# gpio8p5.net
KiCad netlist of a schematic drawn in EAGLE
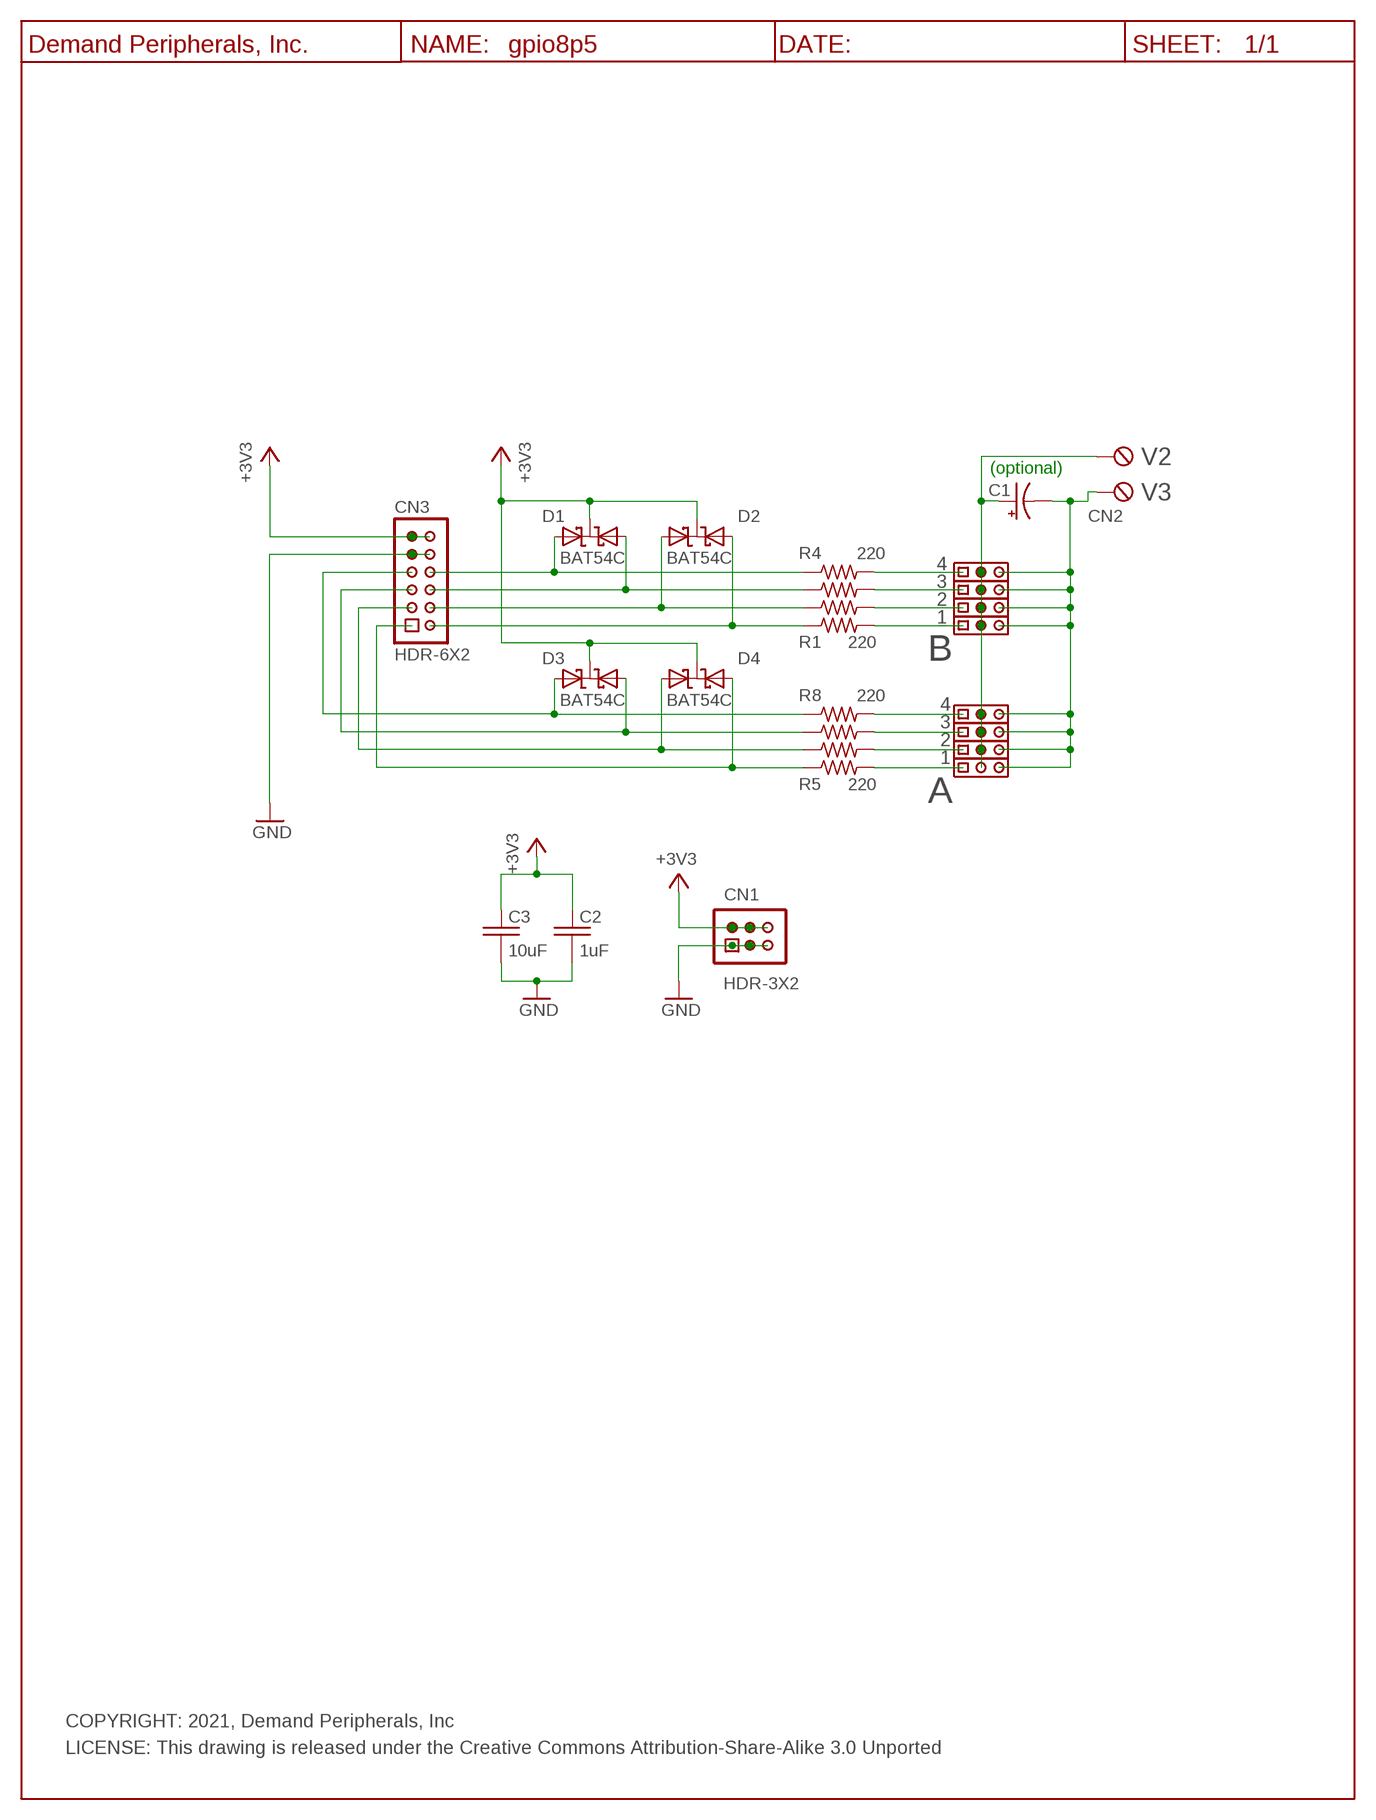
[diagram p0: schematic, sheet 1]

(export (version "E")
  (design (tool "Eeschema 10.0.6"))
  (components
    (comp (ref "C1")
      (value "100uF")
      (footprint "eagle-import:E3.5-8")
      (libsource (lib "eagle-import") (part "C100UF_E3.5-8"))
    )
    (comp (ref "C2")
      (value "1uF")
      (footprint "eagle-import:C0603")
      (libsource (lib "eagle-import") (part "C1.0UF_C0603"))
    )
    (comp (ref "C3")
      (value "10uF")
      (footprint "eagle-import:C1206")
      (libsource (lib "eagle-import") (part "C10UF25V_C1206"))
    )
    (comp (ref "CN1")
      (value "HDR-3X2")
      (footprint "eagle-import:HDR-3X2")
      (libsource (lib "eagle-import") (part "HDR-3X2"))
    )
    (comp (ref "CN2")
      (value "TBLK-5.08-X2")
      (footprint "eagle-import:TBLK-5.08-X2")
      (libsource (lib "eagle-import") (part "TBLK-5.08-X2"))
    )
    (comp (ref "CN3")
      (value "HDR-6X2")
      (footprint "eagle-import:HDR-6X2")
      (libsource (lib "eagle-import") (part "HDR-6X2"))
    )
    (comp (ref "D1")
      (value "BAT54C")
      (footprint "eagle-import:SOT23")
      (libsource (lib "eagle-import") (part "BAT54C"))
    )
    (comp (ref "D2")
      (value "BAT54C")
      (footprint "eagle-import:SOT23")
      (libsource (lib "eagle-import") (part "BAT54C"))
    )
    (comp (ref "D3")
      (value "BAT54C")
      (footprint "eagle-import:SOT23")
      (libsource (lib "eagle-import") (part "BAT54C"))
    )
    (comp (ref "D4")
      (value "BAT54C")
      (footprint "eagle-import:SOT23")
      (libsource (lib "eagle-import") (part "BAT54C"))
    )
    (comp (ref "R1")
      (value "220")
      (footprint "eagle-import:R0603")
      (libsource (lib "eagle-import") (part "R220_R0603"))
    )
    (comp (ref "R2")
      (value "220")
      (footprint "eagle-import:R0603")
      (libsource (lib "eagle-import") (part "R220_R0603"))
    )
    (comp (ref "R3")
      (value "220")
      (footprint "eagle-import:R0603")
      (libsource (lib "eagle-import") (part "R220_R0603"))
    )
    (comp (ref "R4")
      (value "220")
      (footprint "eagle-import:R0603")
      (libsource (lib "eagle-import") (part "R220_R0603"))
    )
    (comp (ref "R5")
      (value "220")
      (footprint "eagle-import:R0603")
      (libsource (lib "eagle-import") (part "R220_R0603"))
    )
    (comp (ref "R6")
      (value "220")
      (footprint "eagle-import:R0603")
      (libsource (lib "eagle-import") (part "R220_R0603"))
    )
    (comp (ref "R7")
      (value "220")
      (footprint "eagle-import:R0603")
      (libsource (lib "eagle-import") (part "R220_R0603"))
    )
    (comp (ref "R8")
      (value "220")
      (footprint "eagle-import:R0603")
      (libsource (lib "eagle-import") (part "R220_R0603"))
    )
    (comp (ref "U$1")
      (value "DP_FRAME_P")
      (footprint "eagle-import:P_FRAME")
      (libsource (lib "eagle-import") (part "DP_FRAME_P"))
    )
    (comp (ref "U$5")
      (value "HDR-3X1")
      (footprint "eagle-import:HDR-3X1")
      (libsource (lib "eagle-import") (part "HDR-3X1"))
    )
    (comp (ref "U$6")
      (value "HDR-3X1")
      (footprint "eagle-import:HDR-3X1")
      (libsource (lib "eagle-import") (part "HDR-3X1"))
    )
    (comp (ref "U$7")
      (value "HDR-3X1")
      (footprint "eagle-import:HDR-3X1")
      (libsource (lib "eagle-import") (part "HDR-3X1"))
    )
    (comp (ref "U$9")
      (value "HDR-3X1")
      (footprint "eagle-import:HDR-3X1")
      (libsource (lib "eagle-import") (part "HDR-3X1"))
    )
    (comp (ref "U$10")
      (value "HDR-3X1")
      (footprint "eagle-import:HDR-3X1")
      (libsource (lib "eagle-import") (part "HDR-3X1"))
    )
    (comp (ref "U$11")
      (value "HDR-3X1")
      (footprint "eagle-import:HDR-3X1")
      (libsource (lib "eagle-import") (part "HDR-3X1"))
    )
    (comp (ref "U$12")
      (value "HDR-3X1")
      (footprint "eagle-import:HDR-3X1")
      (libsource (lib "eagle-import") (part "HDR-3X1"))
    )
    (comp (ref "U$13")
      (value "HDR-3X1")
      (footprint "eagle-import:HDR-3X1")
      (libsource (lib "eagle-import") (part "HDR-3X1"))
    )
  )
  (nets
    (net (code "1") (name "+3V3") (class "Default")
      (node (ref "C2") (pin "1") (pinfunction "1_1") (pintype "passive"))
      (node (ref "C3") (pin "1") (pinfunction "1_1") (pintype "passive"))
      (node (ref "CN1") (pin "2") (pinfunction "2_2") (pintype "passive"))
      (node (ref "CN1") (pin "4") (pinfunction "4_4") (pintype "passive"))
      (node (ref "CN1") (pin "6") (pinfunction "6_6") (pintype "passive"))
      (node (ref "CN3") (pin "11") (pinfunction "11_11") (pintype "passive"))
      (node (ref "CN3") (pin "12") (pinfunction "12_12") (pintype "passive"))
      (node (ref "D1") (pin "3") (pinfunction "CC_3") (pintype "passive"))
      (node (ref "D2") (pin "3") (pinfunction "CC_3") (pintype "passive"))
      (node (ref "D3") (pin "3") (pinfunction "CC_3") (pintype "passive"))
      (node (ref "D4") (pin "3") (pinfunction "CC_3") (pintype "passive"))
    )
    (net (code "2") (name "GND") (class "Default")
      (node (ref "C2") (pin "2") (pinfunction "2_2") (pintype "passive"))
      (node (ref "C3") (pin "2") (pinfunction "2_2") (pintype "passive"))
      (node (ref "CN1") (pin "1") (pinfunction "1_1") (pintype "passive"))
      (node (ref "CN1") (pin "3") (pinfunction "3_3") (pintype "passive"))
      (node (ref "CN1") (pin "5") (pinfunction "5_5") (pintype "passive"))
      (node (ref "CN3") (pin "10") (pinfunction "10_10") (pintype "passive"))
      (node (ref "CN3") (pin "9") (pinfunction "9_9") (pintype "passive"))
    )
    (net (code "3") (name "Net-(CN2-KL)") (class "Default")
      (node (ref "C1") (pin "-") (pinfunction "-_-") (pintype "passive"))
      (node (ref "CN2") (pin "1") (pinfunction "KL_1") (pintype "passive"))
      (node (ref "U$10") (pin "3") (pinfunction "3_3") (pintype "passive"))
      (node (ref "U$11") (pin "3") (pinfunction "3_3") (pintype "passive"))
      (node (ref "U$12") (pin "3") (pinfunction "3_3") (pintype "passive"))
      (node (ref "U$13") (pin "3") (pinfunction "3_3") (pintype "passive"))
      (node (ref "U$5") (pin "3") (pinfunction "3_3") (pintype "passive"))
      (node (ref "U$6") (pin "3") (pinfunction "3_3") (pintype "passive"))
      (node (ref "U$7") (pin "3") (pinfunction "3_3") (pintype "passive"))
      (node (ref "U$9") (pin "3") (pinfunction "3_3") (pintype "passive"))
    )
    (net (code "4") (name "Net-(CN2-KL1)") (class "Default")
      (node (ref "C1") (pin "+") (pinfunction "+_+") (pintype "passive"))
      (node (ref "CN2") (pin "2") (pinfunction "KL1_2") (pintype "passive"))
      (node (ref "U$10") (pin "2") (pinfunction "2_2") (pintype "passive"))
      (node (ref "U$11") (pin "2") (pinfunction "2_2") (pintype "passive"))
      (node (ref "U$12") (pin "2") (pinfunction "2_2") (pintype "passive"))
      (node (ref "U$13") (pin "2") (pinfunction "2_2") (pintype "passive"))
      (node (ref "U$5") (pin "2") (pinfunction "2_2") (pintype "passive"))
      (node (ref "U$6") (pin "2") (pinfunction "2_2") (pintype "passive"))
      (node (ref "U$7") (pin "2") (pinfunction "2_2") (pintype "passive"))
      (node (ref "U$9") (pin "2") (pinfunction "2_2") (pintype "passive"))
    )
    (net (code "5") (name "Net-(D1-A)") (class "Default")
      (node (ref "CN3") (pin "6") (pinfunction "6_6") (pintype "passive"))
      (node (ref "D1") (pin "2") (pinfunction "A_2") (pintype "passive"))
      (node (ref "R3") (pin "1") (pinfunction "1_1") (pintype "passive"))
    )
    (net (code "6") (name "Net-(D1-A1)") (class "Default")
      (node (ref "CN3") (pin "8") (pinfunction "8_8") (pintype "passive"))
      (node (ref "D1") (pin "1") (pinfunction "A1_1") (pintype "passive"))
      (node (ref "R4") (pin "1") (pinfunction "1_1") (pintype "passive"))
    )
    (net (code "7") (name "Net-(D2-A)") (class "Default")
      (node (ref "CN3") (pin "2") (pinfunction "2_2") (pintype "passive"))
      (node (ref "D2") (pin "2") (pinfunction "A_2") (pintype "passive"))
      (node (ref "R1") (pin "1") (pinfunction "1_1") (pintype "passive"))
    )
    (net (code "8") (name "Net-(D2-A1)") (class "Default")
      (node (ref "CN3") (pin "4") (pinfunction "4_4") (pintype "passive"))
      (node (ref "D2") (pin "1") (pinfunction "A1_1") (pintype "passive"))
      (node (ref "R2") (pin "1") (pinfunction "1_1") (pintype "passive"))
    )
    (net (code "9") (name "Net-(D3-A)") (class "Default")
      (node (ref "CN3") (pin "5") (pinfunction "5_5") (pintype "passive"))
      (node (ref "D3") (pin "2") (pinfunction "A_2") (pintype "passive"))
      (node (ref "R7") (pin "1") (pinfunction "1_1") (pintype "passive"))
    )
    (net (code "10") (name "Net-(D3-A1)") (class "Default")
      (node (ref "CN3") (pin "7") (pinfunction "7_7") (pintype "passive"))
      (node (ref "D3") (pin "1") (pinfunction "A1_1") (pintype "passive"))
      (node (ref "R8") (pin "1") (pinfunction "1_1") (pintype "passive"))
    )
    (net (code "11") (name "Net-(D4-A)") (class "Default")
      (node (ref "CN3") (pin "1") (pinfunction "1_1") (pintype "passive"))
      (node (ref "D4") (pin "2") (pinfunction "A_2") (pintype "passive"))
      (node (ref "R5") (pin "1") (pinfunction "1_1") (pintype "passive"))
    )
    (net (code "12") (name "Net-(D4-A1)") (class "Default")
      (node (ref "CN3") (pin "3") (pinfunction "3_3") (pintype "passive"))
      (node (ref "D4") (pin "1") (pinfunction "A1_1") (pintype "passive"))
      (node (ref "R6") (pin "1") (pinfunction "1_1") (pintype "passive"))
    )
    (net (code "13") (name "Net-(R1-Pad2)") (class "Default")
      (node (ref "R1") (pin "2") (pinfunction "2_2") (pintype "passive"))
      (node (ref "U$9") (pin "1") (pinfunction "1_1") (pintype "passive"))
    )
    (net (code "14") (name "Net-(R2-Pad2)") (class "Default")
      (node (ref "R2") (pin "2") (pinfunction "2_2") (pintype "passive"))
      (node (ref "U$7") (pin "1") (pinfunction "1_1") (pintype "passive"))
    )
    (net (code "15") (name "Net-(R3-Pad2)") (class "Default")
      (node (ref "R3") (pin "2") (pinfunction "2_2") (pintype "passive"))
      (node (ref "U$6") (pin "1") (pinfunction "1_1") (pintype "passive"))
    )
    (net (code "16") (name "Net-(R4-Pad2)") (class "Default")
      (node (ref "R4") (pin "2") (pinfunction "2_2") (pintype "passive"))
      (node (ref "U$5") (pin "1") (pinfunction "1_1") (pintype "passive"))
    )
    (net (code "17") (name "Net-(R5-Pad2)") (class "Default")
      (node (ref "R5") (pin "2") (pinfunction "2_2") (pintype "passive"))
      (node (ref "U$13") (pin "1") (pinfunction "1_1") (pintype "passive"))
    )
    (net (code "18") (name "Net-(R6-Pad2)") (class "Default")
      (node (ref "R6") (pin "2") (pinfunction "2_2") (pintype "passive"))
      (node (ref "U$12") (pin "1") (pinfunction "1_1") (pintype "passive"))
    )
    (net (code "19") (name "Net-(R7-Pad2)") (class "Default")
      (node (ref "R7") (pin "2") (pinfunction "2_2") (pintype "passive"))
      (node (ref "U$11") (pin "1") (pinfunction "1_1") (pintype "passive"))
    )
    (net (code "20") (name "Net-(R8-Pad2)") (class "Default")
      (node (ref "R8") (pin "2") (pinfunction "2_2") (pintype "passive"))
      (node (ref "U$10") (pin "1") (pinfunction "1_1") (pintype "passive"))
    )
  )
)
